# x-BIMU_Serial_Breakout.net
KiCad netlist of a schematic drawn in EAGLE
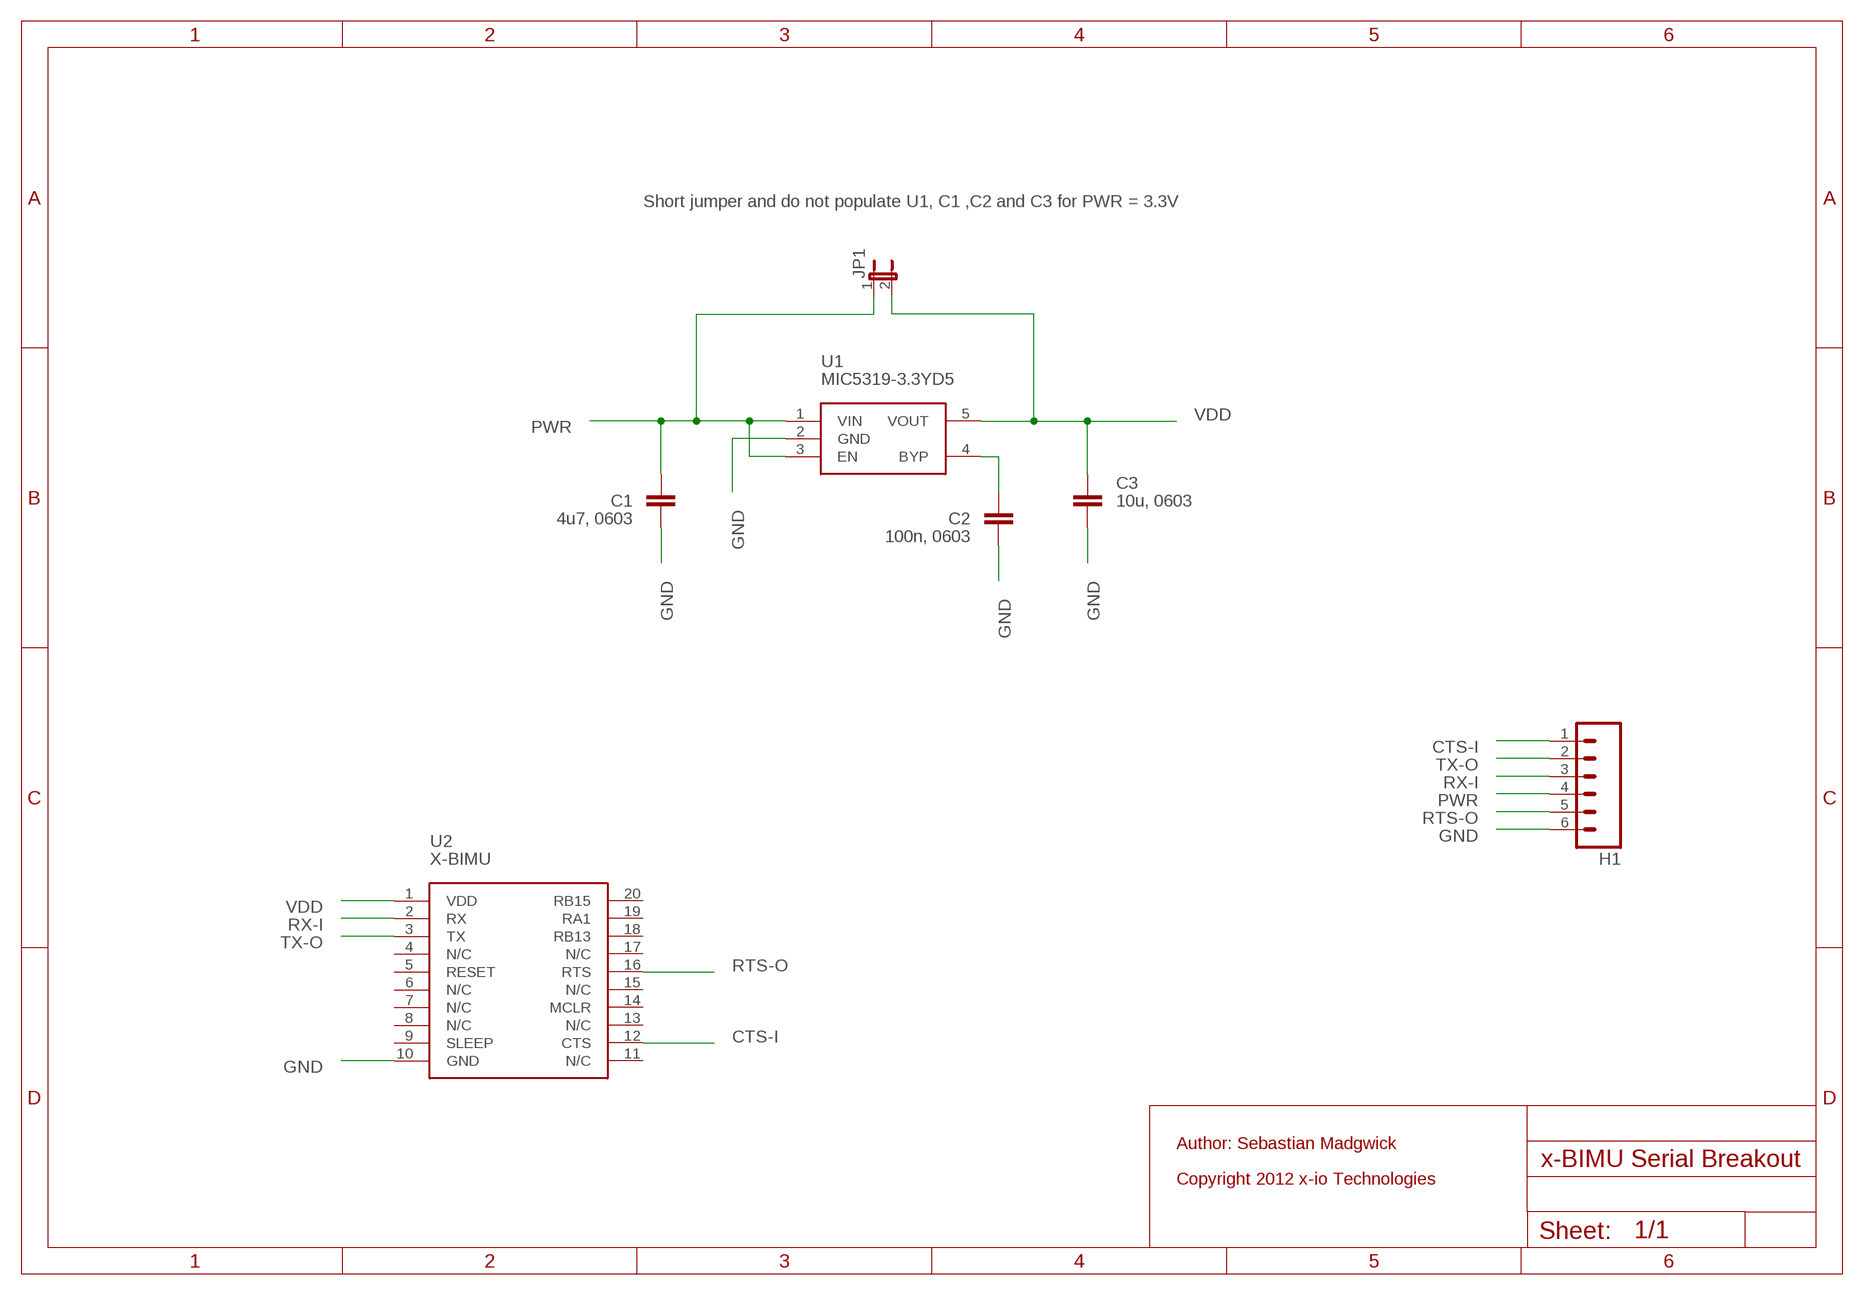
[diagram p0: schematic, sheet 1]

(export (version "E")
  (design (tool "Eeschema 10.0.6"))
  (components
    (comp (ref "C1")
      (value "4u7, 0603")
      (footprint "eagle-import:0402-CAP")
      (libsource (lib "eagle-import") (part "CAP0402-CAP"))
    )
    (comp (ref "C2")
      (value "100n, 0603")
      (footprint "eagle-import:0402-CAP")
      (libsource (lib "eagle-import") (part "CAP0402-CAP"))
    )
    (comp (ref "C3")
      (value "10u, 0603")
      (footprint "eagle-import:0402-CAP")
      (libsource (lib "eagle-import") (part "CAP0402-CAP"))
    )
    (comp (ref "H1")
      (value "M06SMD")
      (footprint "eagle-import:1X06-SMD")
      (libsource (lib "eagle-import") (part "M06SMD"))
    )
    (comp (ref "JP1")
      (value "JUMPER-2SMD-NO")
      (footprint "eagle-import:SJ_2S-NO")
      (libsource (lib "eagle-import") (part "JUMPER-2SMD-NO"))
    )
    (comp (ref "U1")
      (value "MIC5319-3.3YD5")
      (footprint "eagle-import:SOT23-5")
      (libsource (lib "eagle-import") (part "MIC5319"))
    )
    (comp (ref "U2")
      (value "X-BIMU")
      (footprint "eagle-import:X-BIMU_SMD")
      (libsource (lib "eagle-import") (part "X-BIMU"))
    )
  )
  (nets
    (net (code "1") (name "/CTS-I") (class "Default")
      (node (ref "H1") (pin "1") (pinfunction "1_1") (pintype "passive"))
      (node (ref "U2") (pin "12") (pinfunction "CTS_12") (pintype "bidirectional"))
    )
    (net (code "2") (name "/GND") (class "Default")
      (node (ref "C1") (pin "2") (pinfunction "2_2") (pintype "passive"))
      (node (ref "C2") (pin "2") (pinfunction "2_2") (pintype "passive"))
      (node (ref "C3") (pin "2") (pinfunction "2_2") (pintype "passive"))
      (node (ref "H1") (pin "6") (pinfunction "6_6") (pintype "passive"))
      (node (ref "U1") (pin "2") (pinfunction "GND_2") (pintype "bidirectional"))
      (node (ref "U2") (pin "10") (pinfunction "GND_10") (pintype "bidirectional"))
    )
    (net (code "3") (name "/PWR") (class "Default")
      (node (ref "C1") (pin "1") (pinfunction "1_1") (pintype "passive"))
      (node (ref "H1") (pin "4") (pinfunction "4_4") (pintype "passive"))
      (node (ref "JP1") (pin "1") (pinfunction "1_1") (pintype "passive"))
      (node (ref "U1") (pin "1") (pinfunction "VIN_1") (pintype "bidirectional"))
      (node (ref "U1") (pin "3") (pinfunction "EN_3") (pintype "bidirectional"))
    )
    (net (code "4") (name "/RTS-O") (class "Default")
      (node (ref "H1") (pin "5") (pinfunction "5_5") (pintype "passive"))
      (node (ref "U2") (pin "16") (pinfunction "RTS_16") (pintype "bidirectional"))
    )
    (net (code "5") (name "/RX-I") (class "Default")
      (node (ref "H1") (pin "3") (pinfunction "3_3") (pintype "passive"))
      (node (ref "U2") (pin "2") (pinfunction "RX_2") (pintype "bidirectional"))
    )
    (net (code "6") (name "/TX-O") (class "Default")
      (node (ref "H1") (pin "2") (pinfunction "2_2") (pintype "passive"))
      (node (ref "U2") (pin "3") (pinfunction "TX_3") (pintype "bidirectional"))
    )
    (net (code "7") (name "/VDD") (class "Default")
      (node (ref "C3") (pin "1") (pinfunction "1_1") (pintype "passive"))
      (node (ref "JP1") (pin "2") (pinfunction "2_2") (pintype "passive"))
      (node (ref "U1") (pin "5") (pinfunction "VOUT_5") (pintype "bidirectional"))
      (node (ref "U2") (pin "1") (pinfunction "VDD_1") (pintype "bidirectional"))
    )
    (net (code "8") (name "Net-(U1-BYP)") (class "Default")
      (node (ref "C2") (pin "1") (pinfunction "1_1") (pintype "passive"))
      (node (ref "U1") (pin "4") (pinfunction "BYP_4") (pintype "bidirectional"))
    )
    (net (code "9") (name "unconnected-(U2-MCLR-Pad14)") (class "Default")
      (node (ref "U2") (pin "14") (pinfunction "MCLR_14") (pintype "bidirectional"))
    )
    (net (code "10") (name "unconnected-(U2-N{slash}C-Pad4)") (class "Default")
      (node (ref "U2") (pin "4") (pinfunction "N/C_4") (pintype "bidirectional"))
    )
    (net (code "11") (name "unconnected-(U2-N{slash}C-Pad6)") (class "Default")
      (node (ref "U2") (pin "6") (pinfunction "N/C_6") (pintype "bidirectional"))
    )
    (net (code "12") (name "unconnected-(U2-N{slash}C-Pad7)") (class "Default")
      (node (ref "U2") (pin "7") (pinfunction "N/C_7") (pintype "bidirectional"))
    )
    (net (code "13") (name "unconnected-(U2-N{slash}C-Pad8)") (class "Default")
      (node (ref "U2") (pin "8") (pinfunction "N/C_8") (pintype "bidirectional"))
    )
    (net (code "14") (name "unconnected-(U2-N{slash}C-Pad11)") (class "Default")
      (node (ref "U2") (pin "11") (pinfunction "N/C_11") (pintype "bidirectional"))
    )
    (net (code "15") (name "unconnected-(U2-N{slash}C-Pad13)") (class "Default")
      (node (ref "U2") (pin "13") (pinfunction "N/C_13") (pintype "bidirectional"))
    )
    (net (code "16") (name "unconnected-(U2-N{slash}C-Pad15)") (class "Default")
      (node (ref "U2") (pin "15") (pinfunction "N/C_15") (pintype "bidirectional"))
    )
    (net (code "17") (name "unconnected-(U2-N{slash}C-Pad17)") (class "Default")
      (node (ref "U2") (pin "17") (pinfunction "N/C_17") (pintype "bidirectional"))
    )
    (net (code "18") (name "unconnected-(U2-RA1-Pad19)") (class "Default")
      (node (ref "U2") (pin "19") (pinfunction "RA1_19") (pintype "bidirectional"))
    )
    (net (code "19") (name "unconnected-(U2-RB13-Pad18)") (class "Default")
      (node (ref "U2") (pin "18") (pinfunction "RB13_18") (pintype "bidirectional"))
    )
    (net (code "20") (name "unconnected-(U2-RB15-Pad20)") (class "Default")
      (node (ref "U2") (pin "20") (pinfunction "RB15_20") (pintype "bidirectional"))
    )
    (net (code "21") (name "unconnected-(U2-RESET-Pad5)") (class "Default")
      (node (ref "U2") (pin "5") (pinfunction "RESET_5") (pintype "bidirectional"))
    )
    (net (code "22") (name "unconnected-(U2-SLEEP-Pad9)") (class "Default")
      (node (ref "U2") (pin "9") (pinfunction "SLEEP_9") (pintype "bidirectional"))
    )
  )
)
